# ATU_RF.net
KiCad netlist of a schematic drawn in Altium Designer
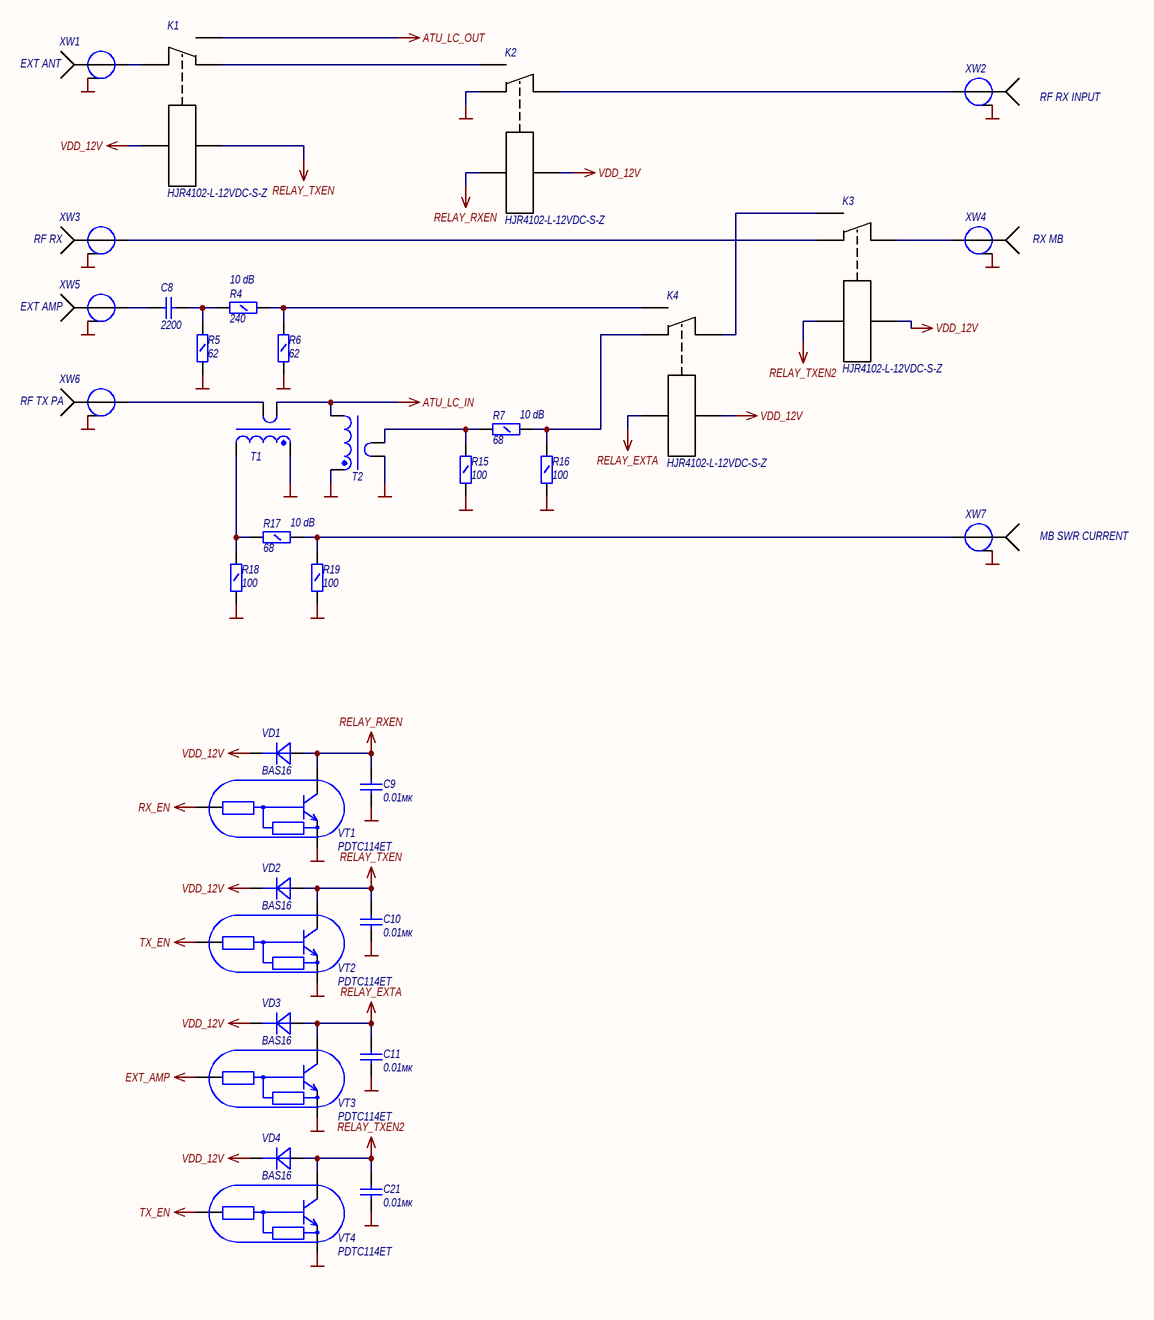
[diagram p0: ATU_RF.SchDoc]

(export (version "E")
  (design (tool "Eeschema 10.0.6"))
  (components
    (comp (ref "C8")
      (value "2200")
      (footprint "CAPC3216X19L")
      (description "Кер. ЧИП-конденсатор")
      (fields (field (name "MANUFACTURER") "WALSIN") (field (name "TOLERANCE") "±10%"))
      (libsource (lib "nels_caps") (part "Кер.ЧИП конд. 1206 2200пФ X7К 10% 1000В"))
    )
    (comp (ref "C9")
      (value "0.01мк")
      (footprint "CAPC1005X06N")
      (description "Кер. ЧИП-конденсатор")
      (fields (field (name "TOLERANCE") "±20%"))
      (libsource (lib "nels_caps") (part "Кер.ЧИП конд. 0402 0.01мкФ X7R 10%, 50В"))
    )
    (comp (ref "C10")
      (value "0.01мк")
      (footprint "CAPC1005X06N")
      (description "Кер. ЧИП-конденсатор")
      (fields (field (name "TOLERANCE") "±20%"))
      (libsource (lib "nels_caps") (part "Кер.ЧИП конд. 0402 0.01мкФ X7R 10%, 50В"))
    )
    (comp (ref "C11")
      (value "0.01мк")
      (footprint "CAPC1005X06N")
      (description "Кер. ЧИП-конденсатор")
      (fields (field (name "TOLERANCE") "±20%"))
      (libsource (lib "nels_caps") (part "Кер.ЧИП конд. 0402 0.01мкФ X7R 10%, 50В"))
    )
    (comp (ref "C21")
      (value "0.01мк")
      (footprint "CAPC1005X06N")
      (description "Кер. ЧИП-конденсатор")
      (fields (field (name "TOLERANCE") "±20%"))
      (libsource (lib "nels_caps") (part "Кер.ЧИП конд. 0402 0.01мкФ X7R 10%, 50В"))
    )
    (comp (ref "K1")
      (value "HJR4102-L-12VDC-S-Z")
      (footprint "HJR4102")
      (description "Реле 1пер. 12VDC, 1A/240VAC")
      (libsource (lib "nels_other") (part "Реле HJR4102-L-12VDC-S-Z"))
    )
    (comp (ref "K2")
      (value "HJR4102-L-12VDC-S-Z")
      (footprint "HJR4102")
      (description "Реле 1пер. 12VDC, 1A/240VAC")
      (libsource (lib "nels_other") (part "Реле HJR4102-L-12VDC-S-Z"))
    )
    (comp (ref "K3")
      (value "HJR4102-L-12VDC-S-Z")
      (footprint "HJR4102")
      (description "Реле 1пер. 12VDC, 1A/240VAC")
      (libsource (lib "nels_other") (part "Реле HJR4102-L-12VDC-S-Z"))
    )
    (comp (ref "K4")
      (value "HJR4102-L-12VDC-S-Z")
      (footprint "HJR4102")
      (description "Реле 1пер. 12VDC, 1A/240VAC")
      (libsource (lib "nels_other") (part "Реле HJR4102-L-12VDC-S-Z"))
    )
    (comp (ref "R4")
      (value "240")
      (footprint "RESC3216X04L")
      (description "ЧИП-резистор")
      (fields (field (name "TOLERANCE") "±5%") (field (name "MANUFACTURER") "ROHM"))
      (libsource (lib "nels_res") (part "Чип резистор 1206 240 Ом, 5%"))
    )
    (comp (ref "R5")
      (value "62")
      (footprint "RESC3216X04L")
      (description "ЧИП-резистор")
      (fields (field (name "TOLERANCE") "±5%") (field (name "MANUFACTURER") "ROHM"))
      (libsource (lib "nels_res") (part "Чип резистор 1206 62 Ом, 5%"))
    )
    (comp (ref "R6")
      (value "62")
      (footprint "RESC3216X04L")
      (description "ЧИП-резистор")
      (fields (field (name "TOLERANCE") "±5%") (field (name "MANUFACTURER") "ROHM"))
      (libsource (lib "nels_res") (part "Чип резистор 1206 62 Ом, 5%"))
    )
    (comp (ref "R7")
      (value "68")
      (footprint "RESC3216X04L")
      (description "ЧИП-резистор")
      (fields (field (name "TOLERANCE") "±5%") (field (name "MANUFACTURER") "ROHM"))
      (libsource (lib "nels_res") (part "Чип резистор 1206 68 Ом, 5%"))
    )
    (comp (ref "R15")
      (value "100")
      (footprint "RESC3216X04L")
      (description "ЧИП-резистор")
      (fields (field (name "TOLERANCE") "±5%") (field (name "MANUFACTURER") "ROHM"))
      (libsource (lib "nels_res") (part "Чип резистор 1206 100 Ом, 5%"))
    )
    (comp (ref "R16")
      (value "100")
      (footprint "RESC3216X04L")
      (description "ЧИП-резистор")
      (fields (field (name "TOLERANCE") "±5%") (field (name "MANUFACTURER") "ROHM"))
      (libsource (lib "nels_res") (part "Чип резистор 1206 100 Ом, 5%"))
    )
    (comp (ref "R17")
      (value "68")
      (footprint "RESC3216X04L")
      (description "ЧИП-резистор")
      (fields (field (name "TOLERANCE") "±5%") (field (name "MANUFACTURER") "ROHM"))
      (libsource (lib "nels_res") (part "Чип резистор 1206 68 Ом, 5%"))
    )
    (comp (ref "R18")
      (value "100")
      (footprint "RESC3216X04L")
      (description "ЧИП-резистор")
      (fields (field (name "TOLERANCE") "±5%") (field (name "MANUFACTURER") "ROHM"))
      (libsource (lib "nels_res") (part "Чип резистор 1206 100 Ом, 5%"))
    )
    (comp (ref "R19")
      (value "100")
      (footprint "RESC3216X04L")
      (description "ЧИП-резистор")
      (fields (field (name "TOLERANCE") "±5%") (field (name "MANUFACTURER") "ROHM"))
      (libsource (lib "nels_res") (part "Чип резистор 1206 100 Ом, 5%"))
    )
    (comp (ref "T1")
      (value "Трансформатор SWR_CURRENT")
      (footprint "TRSF PA CURRENT")
      (libsource (lib "nels_ind") (part "Трансформатор SWR_CURRENT"))
    )
    (comp (ref "T2")
      (value "Трансформатор SWR_VOLTAGE")
      (footprint "TRSF PA VOLTAGE")
      (libsource (lib "nels_ind") (part "Трансформатор SWR_VOLTAGE"))
    )
    (comp (ref "VD1")
      (value "BAS16")
      (footprint "SOT23_N")
      (description "High-speed switching diodes")
      (fields (field (name "MANUFACTURER") "Nexperia"))
      (libsource (lib "nels_other") (part "ЧИП диод BAS16"))
    )
    (comp (ref "VD2")
      (value "BAS16")
      (footprint "SOT23_N")
      (description "High-speed switching diodes")
      (fields (field (name "MANUFACTURER") "Nexperia"))
      (libsource (lib "nels_other") (part "ЧИП диод BAS16"))
    )
    (comp (ref "VD3")
      (value "BAS16")
      (footprint "SOT23_N")
      (description "High-speed switching diodes")
      (fields (field (name "MANUFACTURER") "Nexperia"))
      (libsource (lib "nels_other") (part "ЧИП диод BAS16"))
    )
    (comp (ref "VD4")
      (value "BAS16")
      (footprint "SOT23_N")
      (description "High-speed switching diodes")
      (fields (field (name "MANUFACTURER") "Nexperia"))
      (libsource (lib "nels_other") (part "ЧИП диод BAS16"))
    )
    (comp (ref "VT1")
      (value "PDTC114ET")
      (footprint "SOT23_N")
      (description "NPN resistor-equipped transistors;  R1 = 10 k, R2 = 10")
      (libsource (lib "nels_other") (part "ЧИП транзистор PDTC114ET"))
    )
    (comp (ref "VT2")
      (value "PDTC114ET")
      (footprint "SOT23_N")
      (description "NPN resistor-equipped transistors;  R1 = 10 k, R2 = 10")
      (libsource (lib "nels_other") (part "ЧИП транзистор PDTC114ET"))
    )
    (comp (ref "VT3")
      (value "PDTC114ET")
      (footprint "SOT23_N")
      (description "NPN resistor-equipped transistors;  R1 = 10 k, R2 = 10")
      (libsource (lib "nels_other") (part "ЧИП транзистор PDTC114ET"))
    )
    (comp (ref "VT4")
      (value "PDTC114ET")
      (footprint "SOT23_N")
      (description "NPN resistor-equipped transistors;  R1 = 10 k, R2 = 10")
      (libsource (lib "nels_other") (part "ЧИП транзистор PDTC114ET"))
    )
    (comp (ref "XW1")
      (value "SMA-JR")
      (footprint "SMA-JR")
      (description "SMA-JR Разъем SMA гнездо на плату, прямой угол")
      (libsource (lib "nels_conn") (part "Соединитель коаксиальный SMA-JR"))
    )
    (comp (ref "XW2")
      (value "SMA-JR")
      (footprint "SMA-JR")
      (description "SMA-JR Разъем SMA гнездо на плату, прямой угол")
      (libsource (lib "") (part "Соединитель коаксиальный SMA-JR_1"))
    )
    (comp (ref "XW3")
      (value "SMA-JR")
      (footprint "SMA-JR")
      (description "SMA-JR Разъем SMA гнездо на плату, прямой угол")
      (libsource (lib "nels_conn") (part "Соединитель коаксиальный SMA-JR"))
    )
    (comp (ref "XW4")
      (value "SMA-JR")
      (footprint "SMA-JR")
      (description "SMA-JR Разъем SMA гнездо на плату, прямой угол")
      (libsource (lib "") (part "Соединитель коаксиальный SMA-JR_1"))
    )
    (comp (ref "XW5")
      (value "SMA-JR")
      (footprint "SMA-JR")
      (description "SMA-JR Разъем SMA гнездо на плату, прямой угол")
      (libsource (lib "nels_conn") (part "Соединитель коаксиальный SMA-JR"))
    )
    (comp (ref "XW6")
      (value "SMA-JR")
      (footprint "SMA-JR")
      (description "SMA-JR Разъем SMA гнездо на плату, прямой угол")
      (libsource (lib "nels_conn") (part "Соединитель коаксиальный SMA-JR"))
    )
    (comp (ref "XW7")
      (value "SMA-JR")
      (footprint "SMA-JR")
      (description "SMA-JR Разъем SMA гнездо на плату, прямой угол")
      (libsource (lib "") (part "Соединитель коаксиальный SMA-JR_1"))
    )
  )
  (nets
    (net (code "1") (name "ATU_LC_IN") (class "Default")
      (node (ref "T1") (pin "1") (pinfunction "4_1") (pintype "passive"))
      (node (ref "T2") (pin "4") (pintype "passive"))
    )
    (net (code "2") (name "ATU_LC_OUT") (class "Default") (node (ref "K1") (pin "6") (pintype "passive")))
    (net (code "3") (name "EXT_AMP") (class "Default")
      (node (ref "VT3") (pin "1") (pinfunction "B_1") (pintype "passive"))
    )
    (net (code "4") (name "GND") (class "Default")
      (node (ref "C10") (pin "1") (pinfunction "1_1") (pintype "passive"))
      (node (ref "C11") (pin "1") (pinfunction "1_1") (pintype "passive"))
      (node (ref "C21") (pin "1") (pinfunction "1_1") (pintype "passive"))
      (node (ref "C9") (pin "1") (pinfunction "1_1") (pintype "passive"))
      (node (ref "K2") (pin "7") (pintype "passive"))
      (node (ref "R15") (pin "1") (pinfunction "1_1") (pintype "passive"))
      (node (ref "R16") (pin "1") (pinfunction "1_1") (pintype "passive"))
      (node (ref "R18") (pin "1") (pinfunction "1_1") (pintype "passive"))
      (node (ref "R19") (pin "1") (pinfunction "1_1") (pintype "passive"))
      (node (ref "R5") (pin "1") (pinfunction "1_1") (pintype "passive"))
      (node (ref "R6") (pin "1") (pinfunction "1_1") (pintype "passive"))
      (node (ref "T1") (pin "3") (pintype "passive"))
      (node (ref "T2") (pin "1") (pinfunction "4_1") (pintype "passive"))
      (node (ref "T2") (pin "3") (pintype "passive"))
      (node (ref "VT1") (pin "2") (pinfunction "E_2") (pintype "passive"))
      (node (ref "VT2") (pin "2") (pinfunction "E_2") (pintype "passive"))
      (node (ref "VT3") (pin "2") (pinfunction "E_2") (pintype "passive"))
      (node (ref "VT4") (pin "2") (pinfunction "E_2") (pintype "passive"))
      (node (ref "XW1") (pin "2") (pinfunction "2_2") (pintype "passive"))
      (node (ref "XW2") (pin "2") (pinfunction "2_2") (pintype "passive"))
      (node (ref "XW3") (pin "2") (pinfunction "2_2") (pintype "passive"))
      (node (ref "XW4") (pin "2") (pinfunction "2_2") (pintype "passive"))
      (node (ref "XW5") (pin "2") (pinfunction "2_2") (pintype "passive"))
      (node (ref "XW6") (pin "2") (pinfunction "2_2") (pintype "passive"))
      (node (ref "XW7") (pin "2") (pinfunction "2_2") (pintype "passive"))
    )
    (net (code "5") (name "Net-(C8-Pad1)") (class "Default")
      (node (ref "C8") (pin "1") (pinfunction "1_1") (pintype "passive"))
      (node (ref "R4") (pin "1") (pinfunction "1_1") (pintype "passive"))
      (node (ref "R5") (pin "2") (pinfunction "2_2") (pintype "passive"))
    )
    (net (code "6") (name "Net-(C8-Pad2)") (class "Default")
      (node (ref "C8") (pin "2") (pinfunction "2_2") (pintype "passive"))
      (node (ref "XW5") (pin "1") (pinfunction "1_1") (pintype "passive"))
    )
    (net (code "7") (name "Net-(K1-Pad1)") (class "Default")
      (node (ref "K1") (pin "1") (pintype "passive"))
      (node (ref "XW1") (pin "1") (pinfunction "1_1") (pintype "passive"))
    )
    (net (code "8") (name "Net-(K1-Pad7)") (class "Default")
      (node (ref "K1") (pin "7") (pintype "passive"))
      (node (ref "K2") (pin "6") (pintype "passive"))
    )
    (net (code "9") (name "Net-(K2-Pad1)") (class "Default")
      (node (ref "K2") (pin "1") (pintype "passive"))
      (node (ref "XW2") (pin "1") (pinfunction "1_1") (pintype "passive"))
    )
    (net (code "10") (name "Net-(K3-Pad1)") (class "Default")
      (node (ref "K3") (pin "1") (pintype "passive"))
      (node (ref "XW4") (pin "1") (pinfunction "1_1") (pintype "passive"))
    )
    (net (code "11") (name "Net-(K3-Pad6)") (class "Default")
      (node (ref "K3") (pin "6") (pintype "passive"))
      (node (ref "K4") (pin "1") (pintype "passive"))
    )
    (net (code "12") (name "Net-(K3-Pad7)") (class "Default")
      (node (ref "K3") (pin "7") (pintype "passive"))
      (node (ref "XW3") (pin "1") (pinfunction "1_1") (pintype "passive"))
    )
    (net (code "13") (name "Net-(K4-Pad6)") (class "Default")
      (node (ref "K4") (pin "6") (pintype "passive"))
      (node (ref "R4") (pin "2") (pinfunction "2_2") (pintype "passive"))
      (node (ref "R6") (pin "2") (pinfunction "2_2") (pintype "passive"))
    )
    (net (code "14") (name "Net-(K4-Pad7)") (class "Default")
      (node (ref "K4") (pin "7") (pintype "passive"))
      (node (ref "R16") (pin "2") (pinfunction "2_2") (pintype "passive"))
      (node (ref "R7") (pin "2") (pinfunction "2_2") (pintype "passive"))
    )
    (net (code "15") (name "Net-(R15-Pad2)") (class "Default")
      (node (ref "R15") (pin "2") (pinfunction "2_2") (pintype "passive"))
      (node (ref "R7") (pin "1") (pinfunction "1_1") (pintype "passive"))
      (node (ref "T2") (pin "2") (pintype "passive"))
    )
    (net (code "16") (name "Net-(R17-Pad1)") (class "Default")
      (node (ref "R17") (pin "1") (pinfunction "1_1") (pintype "passive"))
      (node (ref "R18") (pin "2") (pinfunction "2_2") (pintype "passive"))
      (node (ref "T1") (pin "4") (pintype "passive"))
    )
    (net (code "17") (name "Net-(R17-Pad2)") (class "Default")
      (node (ref "R17") (pin "2") (pinfunction "2_2") (pintype "passive"))
      (node (ref "R19") (pin "2") (pinfunction "2_2") (pintype "passive"))
      (node (ref "XW7") (pin "1") (pinfunction "1_1") (pintype "passive"))
    )
    (net (code "18") (name "Net-(T1-Pad2)") (class "Default")
      (node (ref "T1") (pin "2") (pintype "passive"))
      (node (ref "XW6") (pin "1") (pinfunction "1_1") (pintype "passive"))
    )
    (net (code "19") (name "RELAY_EXTA") (class "Default")
      (node (ref "C11") (pin "2") (pinfunction "2_2") (pintype "passive"))
      (node (ref "K4") (pin "5") (pintype "passive"))
      (node (ref "VD3") (pin "1") (pinfunction "A_1") (pintype "passive"))
      (node (ref "VT3") (pin "3") (pinfunction "C_3") (pintype "passive"))
    )
    (net (code "20") (name "RELAY_RXEN") (class "Default")
      (node (ref "C9") (pin "2") (pinfunction "2_2") (pintype "passive"))
      (node (ref "K2") (pin "5") (pintype "passive"))
      (node (ref "VD1") (pin "1") (pinfunction "A_1") (pintype "passive"))
      (node (ref "VT1") (pin "3") (pinfunction "C_3") (pintype "passive"))
    )
    (net (code "21") (name "RELAY_TXEN") (class "Default")
      (node (ref "C10") (pin "2") (pinfunction "2_2") (pintype "passive"))
      (node (ref "K1") (pin "5") (pintype "passive"))
      (node (ref "VD2") (pin "1") (pinfunction "A_1") (pintype "passive"))
      (node (ref "VT2") (pin "3") (pinfunction "C_3") (pintype "passive"))
    )
    (net (code "22") (name "RELAY_TXEN2") (class "Default")
      (node (ref "C21") (pin "2") (pinfunction "2_2") (pintype "passive"))
      (node (ref "K3") (pin "5") (pintype "passive"))
      (node (ref "VD4") (pin "1") (pinfunction "A_1") (pintype "passive"))
      (node (ref "VT4") (pin "3") (pinfunction "C_3") (pintype "passive"))
    )
    (net (code "23") (name "RX_EN") (class "Default")
      (node (ref "VT1") (pin "1") (pinfunction "B_1") (pintype "passive"))
    )
    (net (code "24") (name "TX_EN") (class "Default")
      (node (ref "VT2") (pin "1") (pinfunction "B_1") (pintype "passive"))
      (node (ref "VT4") (pin "1") (pinfunction "B_1") (pintype "passive"))
    )
    (net (code "25") (name "VDD_12V") (class "Default")
      (node (ref "K1") (pin "8") (pintype "passive"))
      (node (ref "K2") (pin "8") (pintype "passive"))
      (node (ref "K3") (pin "8") (pintype "passive"))
      (node (ref "K4") (pin "8") (pintype "passive"))
      (node (ref "VD1") (pin "3") (pinfunction "K_3") (pintype "passive"))
      (node (ref "VD2") (pin "3") (pinfunction "K_3") (pintype "passive"))
      (node (ref "VD3") (pin "3") (pinfunction "K_3") (pintype "passive"))
      (node (ref "VD4") (pin "3") (pinfunction "K_3") (pintype "passive"))
    )
  )
)
